# midi_nubbin.net
KiCad netlist of a schematic drawn in EAGLE
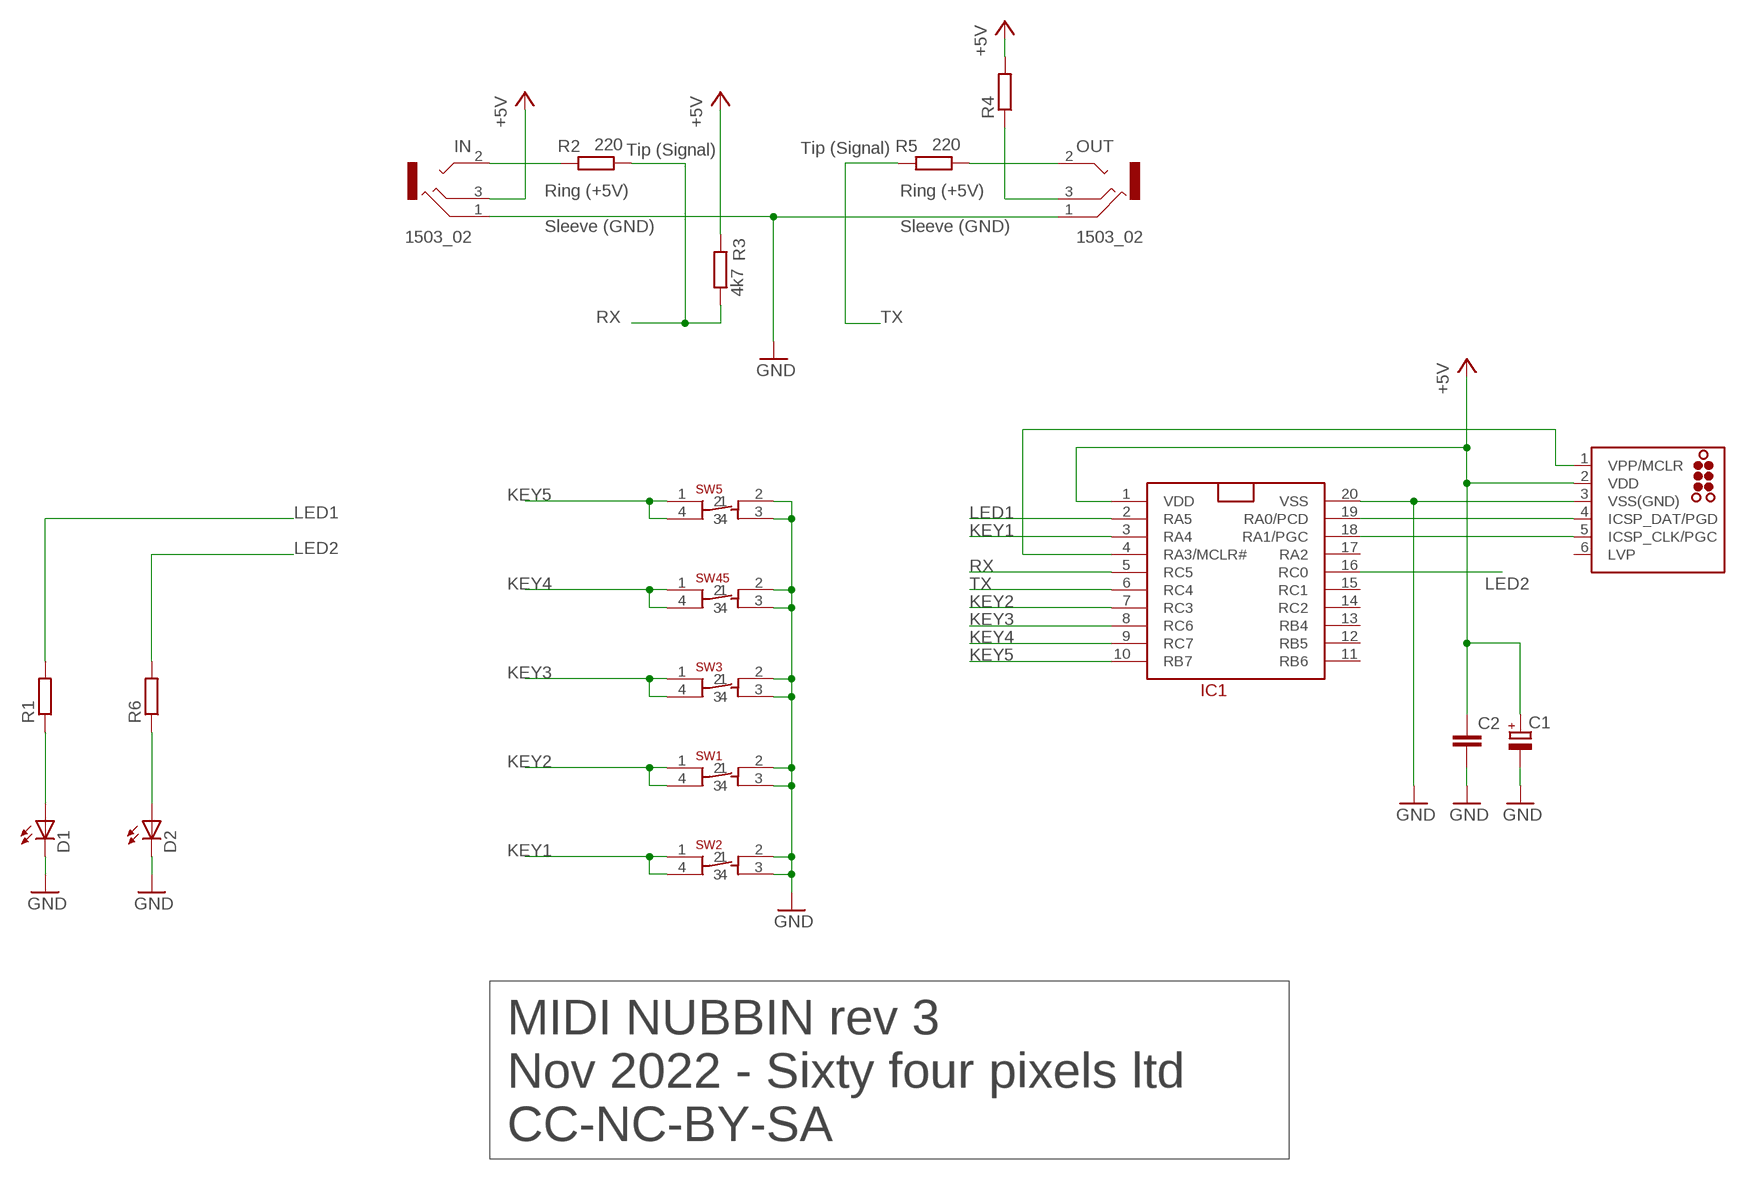
[diagram p0: schematic, sheet 1]

(export (version "E")
  (design (tool "Eeschema 10.0.6"))
  (components
    (comp (ref "C1")
      (value "CPOL-EUSMCB")
      (footprint "eagle-import:SMC_B")
      (libsource (lib "eagle-import") (part "CPOL-EUSMCB"))
    )
    (comp (ref "C2")
      (value "C-EUC0805")
      (footprint "eagle-import:C0805")
      (libsource (lib "eagle-import") (part "C-EUC0805"))
    )
    (comp (ref "D1")
      (value "LEDCHIPLED_0805")
      (footprint "eagle-import:CHIPLED_0805")
      (libsource (lib "eagle-import") (part "LEDCHIPLED_0805"))
    )
    (comp (ref "D2")
      (value "LEDCHIPLED_0805")
      (footprint "eagle-import:CHIPLED_0805")
      (libsource (lib "eagle-import") (part "LEDCHIPLED_0805"))
    )
    (comp (ref "IC1")
      (value "PIC16F15345SSOP20")
      (footprint "eagle-import:SSOP20")
      (libsource (lib "eagle-import") (part "PIC16F15345SSOP20"))
    )
    (comp (ref "ICSP")
      (value "TC2030-MCP-NL")
      (footprint "eagle-import:TC2030-MCP-NL")
      (libsource (lib "eagle-import") (part "TC2030-MCP-NL"))
    )
    (comp (ref "IN")
      (value "1503_02")
      (footprint "eagle-import:1503_02")
      (libsource (lib "eagle-import") (part "1503_02"))
    )
    (comp (ref "OUT")
      (value "1503_02")
      (footprint "eagle-import:1503_02")
      (libsource (lib "eagle-import") (part "1503_02"))
    )
    (comp (ref "R1")
      (value "R-EU_R0805")
      (footprint "eagle-import:R0805")
      (libsource (lib "eagle-import") (part "R-EU_R0805"))
    )
    (comp (ref "R2")
      (value "220")
      (footprint "eagle-import:R0805")
      (libsource (lib "eagle-import") (part "R-EU_R0805"))
    )
    (comp (ref "R3")
      (value "4k7")
      (footprint "eagle-import:R0805")
      (libsource (lib "eagle-import") (part "R-EU_R0805"))
    )
    (comp (ref "R4")
      (value "R-EU_R0805")
      (footprint "eagle-import:R0805")
      (libsource (lib "eagle-import") (part "R-EU_R0805"))
    )
    (comp (ref "R5")
      (value "220")
      (footprint "eagle-import:R0805")
      (libsource (lib "eagle-import") (part "R-EU_R0805"))
    )
    (comp (ref "R6")
      (value "R-EU_R0805")
      (footprint "eagle-import:R0805")
      (libsource (lib "eagle-import") (part "R-EU_R0805"))
    )
    (comp (ref "SW1")
      (value "6MMTACTSMT")
      (footprint "eagle-import:6MMTACTSMT")
      (libsource (lib "eagle-import") (part "6MMTACTSMT"))
    )
    (comp (ref "SW2")
      (value "6MMTACTSMT")
      (footprint "eagle-import:6MMTACTSMT")
      (libsource (lib "eagle-import") (part "6MMTACTSMT"))
    )
    (comp (ref "SW3")
      (value "6MMTACTSMT")
      (footprint "eagle-import:6MMTACTSMT")
      (libsource (lib "eagle-import") (part "6MMTACTSMT"))
    )
    (comp (ref "SW5")
      (value "6MMTACTSMT")
      (footprint "eagle-import:6MMTACTSMT")
      (libsource (lib "eagle-import") (part "6MMTACTSMT"))
    )
    (comp (ref "SW45")
      (value "6MMTACTSMT")
      (footprint "eagle-import:6MMTACTSMT")
      (libsource (lib "eagle-import") (part "6MMTACTSMT"))
    )
  )
  (nets
    (net (code "1") (name "+5V") (class "Default")
      (node (ref "C1") (pin "+") (pinfunction "+_+") (pintype "passive"))
      (node (ref "C2") (pin "1") (pinfunction "1_1") (pintype "passive"))
      (node (ref "IC1") (pin "1") (pinfunction "VDD_1") (pintype "bidirectional"))
      (node (ref "ICSP") (pin "2") (pinfunction "VDD_2") (pintype "power_in"))
      (node (ref "IN") (pin "3") (pinfunction "3_3") (pintype "passive"))
      (node (ref "R3") (pin "2") (pinfunction "2_2") (pintype "passive"))
      (node (ref "R4") (pin "2") (pinfunction "2_2") (pintype "passive"))
    )
    (net (code "2") (name "/KEY1") (class "Default")
      (node (ref "IC1") (pin "3") (pinfunction "RA4_3") (pintype "bidirectional"))
      (node (ref "SW2") (pin "1") (pinfunction "1_1") (pintype "bidirectional"))
      (node (ref "SW2") (pin "4") (pinfunction "4_4") (pintype "bidirectional"))
    )
    (net (code "3") (name "/KEY2") (class "Default")
      (node (ref "IC1") (pin "7") (pinfunction "RC3_7") (pintype "bidirectional"))
      (node (ref "SW1") (pin "1") (pinfunction "1_1") (pintype "bidirectional"))
      (node (ref "SW1") (pin "4") (pinfunction "4_4") (pintype "bidirectional"))
    )
    (net (code "4") (name "/KEY3") (class "Default")
      (node (ref "IC1") (pin "8") (pinfunction "RC6_8") (pintype "bidirectional"))
      (node (ref "SW3") (pin "1") (pinfunction "1_1") (pintype "bidirectional"))
      (node (ref "SW3") (pin "4") (pinfunction "4_4") (pintype "bidirectional"))
    )
    (net (code "5") (name "/KEY4") (class "Default")
      (node (ref "IC1") (pin "9") (pinfunction "RC7_9") (pintype "bidirectional"))
      (node (ref "SW45") (pin "1") (pinfunction "1_1") (pintype "bidirectional"))
      (node (ref "SW45") (pin "4") (pinfunction "4_4") (pintype "bidirectional"))
    )
    (net (code "6") (name "/KEY5") (class "Default")
      (node (ref "IC1") (pin "10") (pinfunction "RB7_10") (pintype "bidirectional"))
      (node (ref "SW5") (pin "1") (pinfunction "1_1") (pintype "bidirectional"))
      (node (ref "SW5") (pin "4") (pinfunction "4_4") (pintype "bidirectional"))
    )
    (net (code "7") (name "/LED1") (class "Default")
      (node (ref "IC1") (pin "2") (pinfunction "RA5_2") (pintype "bidirectional"))
      (node (ref "R1") (pin "2") (pinfunction "2_2") (pintype "passive"))
    )
    (net (code "8") (name "/LED2") (class "Default")
      (node (ref "IC1") (pin "16") (pinfunction "RC0_16") (pintype "bidirectional"))
      (node (ref "R6") (pin "2") (pinfunction "2_2") (pintype "passive"))
    )
    (net (code "9") (name "/RX") (class "Default")
      (node (ref "IC1") (pin "5") (pinfunction "RC5_5") (pintype "bidirectional"))
      (node (ref "R2") (pin "1") (pinfunction "1_1") (pintype "passive"))
      (node (ref "R3") (pin "1") (pinfunction "1_1") (pintype "passive"))
    )
    (net (code "10") (name "/TX") (class "Default")
      (node (ref "IC1") (pin "6") (pinfunction "RC4_6") (pintype "bidirectional"))
      (node (ref "R5") (pin "2") (pinfunction "2_2") (pintype "passive"))
    )
    (net (code "11") (name "GND") (class "Default")
      (node (ref "C1") (pin "-") (pinfunction "-_-") (pintype "passive"))
      (node (ref "C2") (pin "2") (pinfunction "2_2") (pintype "passive"))
      (node (ref "D1") (pin "C") (pinfunction "C_C") (pintype "passive"))
      (node (ref "D2") (pin "C") (pinfunction "C_C") (pintype "passive"))
      (node (ref "IC1") (pin "20") (pinfunction "VSS_20") (pintype "bidirectional"))
      (node (ref "ICSP") (pin "3") (pinfunction "VSS(GND)_3") (pintype "power_in"))
      (node (ref "IN") (pin "1") (pinfunction "1_1") (pintype "passive"))
      (node (ref "OUT") (pin "1") (pinfunction "1_1") (pintype "passive"))
      (node (ref "SW1") (pin "2") (pinfunction "2_2") (pintype "bidirectional"))
      (node (ref "SW1") (pin "3") (pinfunction "3_3") (pintype "bidirectional"))
      (node (ref "SW2") (pin "2") (pinfunction "2_2") (pintype "bidirectional"))
      (node (ref "SW2") (pin "3") (pinfunction "3_3") (pintype "bidirectional"))
      (node (ref "SW3") (pin "2") (pinfunction "2_2") (pintype "bidirectional"))
      (node (ref "SW3") (pin "3") (pinfunction "3_3") (pintype "bidirectional"))
      (node (ref "SW45") (pin "2") (pinfunction "2_2") (pintype "bidirectional"))
      (node (ref "SW45") (pin "3") (pinfunction "3_3") (pintype "bidirectional"))
      (node (ref "SW5") (pin "2") (pinfunction "2_2") (pintype "bidirectional"))
      (node (ref "SW5") (pin "3") (pinfunction "3_3") (pintype "bidirectional"))
    )
    (net (code "12") (name "Net-(D1-PadA)") (class "Default")
      (node (ref "D1") (pin "A") (pinfunction "A_A") (pintype "passive"))
      (node (ref "R1") (pin "1") (pinfunction "1_1") (pintype "passive"))
    )
    (net (code "13") (name "Net-(D2-PadA)") (class "Default")
      (node (ref "D2") (pin "A") (pinfunction "A_A") (pintype "passive"))
      (node (ref "R6") (pin "1") (pinfunction "1_1") (pintype "passive"))
    )
    (net (code "14") (name "Net-(IC1-RA0{slash}PCD)") (class "Default")
      (node (ref "IC1") (pin "19") (pinfunction "RA0/PCD_19") (pintype "bidirectional"))
      (node (ref "ICSP") (pin "4") (pinfunction "ICSP_DAT/PGD_4") (pintype "bidirectional"))
    )
    (net (code "15") (name "Net-(IC1-RA1{slash}PGC)") (class "Default")
      (node (ref "IC1") (pin "18") (pinfunction "RA1/PGC_18") (pintype "bidirectional"))
      (node (ref "ICSP") (pin "5") (pinfunction "ICSP_CLK/PGC_5") (pintype "output"))
    )
    (net (code "16") (name "Net-(IC1-RA3{slash}MCLR#)") (class "Default")
      (node (ref "IC1") (pin "4") (pinfunction "RA3/MCLR#_4") (pintype "bidirectional"))
      (node (ref "ICSP") (pin "1") (pinfunction "VPP/MCLR_1") (pintype "passive"))
    )
    (net (code "17") (name "Net-(IN-Pad2)") (class "Default")
      (node (ref "IN") (pin "2") (pinfunction "2_2") (pintype "passive"))
      (node (ref "R2") (pin "2") (pinfunction "2_2") (pintype "passive"))
    )
    (net (code "18") (name "Net-(OUT-Pad2)") (class "Default")
      (node (ref "OUT") (pin "2") (pinfunction "2_2") (pintype "passive"))
      (node (ref "R5") (pin "1") (pinfunction "1_1") (pintype "passive"))
    )
    (net (code "19") (name "Net-(OUT-Pad3)") (class "Default")
      (node (ref "OUT") (pin "3") (pinfunction "3_3") (pintype "passive"))
      (node (ref "R4") (pin "1") (pinfunction "1_1") (pintype "passive"))
    )
    (net (code "20") (name "unconnected-(IC1-RA2-Pad17)") (class "Default")
      (node (ref "IC1") (pin "17") (pinfunction "RA2_17") (pintype "bidirectional"))
    )
    (net (code "21") (name "unconnected-(IC1-RB4-Pad13)") (class "Default")
      (node (ref "IC1") (pin "13") (pinfunction "RB4_13") (pintype "bidirectional"))
    )
    (net (code "22") (name "unconnected-(IC1-RB5-Pad12)") (class "Default")
      (node (ref "IC1") (pin "12") (pinfunction "RB5_12") (pintype "bidirectional"))
    )
    (net (code "23") (name "unconnected-(IC1-RB6-Pad11)") (class "Default")
      (node (ref "IC1") (pin "11") (pinfunction "RB6_11") (pintype "bidirectional"))
    )
    (net (code "24") (name "unconnected-(IC1-RC1-Pad15)") (class "Default")
      (node (ref "IC1") (pin "15") (pinfunction "RC1_15") (pintype "bidirectional"))
    )
    (net (code "25") (name "unconnected-(IC1-RC2-Pad14)") (class "Default")
      (node (ref "IC1") (pin "14") (pinfunction "RC2_14") (pintype "bidirectional"))
    )
    (net (code "26") (name "unconnected-(ICSP-LVP-Pad6)") (class "Default")
      (node (ref "ICSP") (pin "6") (pinfunction "LVP_6") (pintype "bidirectional"))
    )
    (net (code "27") (name "unconnected-(IN-2-Pad2@2)") (class "Default")
      (node (ref "IN") (pin "2@2") (pinfunction "2_2@2") (pintype "passive"))
    )
    (net (code "28") (name "unconnected-(OUT-2-Pad2@2)") (class "Default")
      (node (ref "OUT") (pin "2@2") (pinfunction "2_2@2") (pintype "passive"))
    )
  )
)
